# rechiever.net
KiCad netlist of a schematic drawn in EAGLE
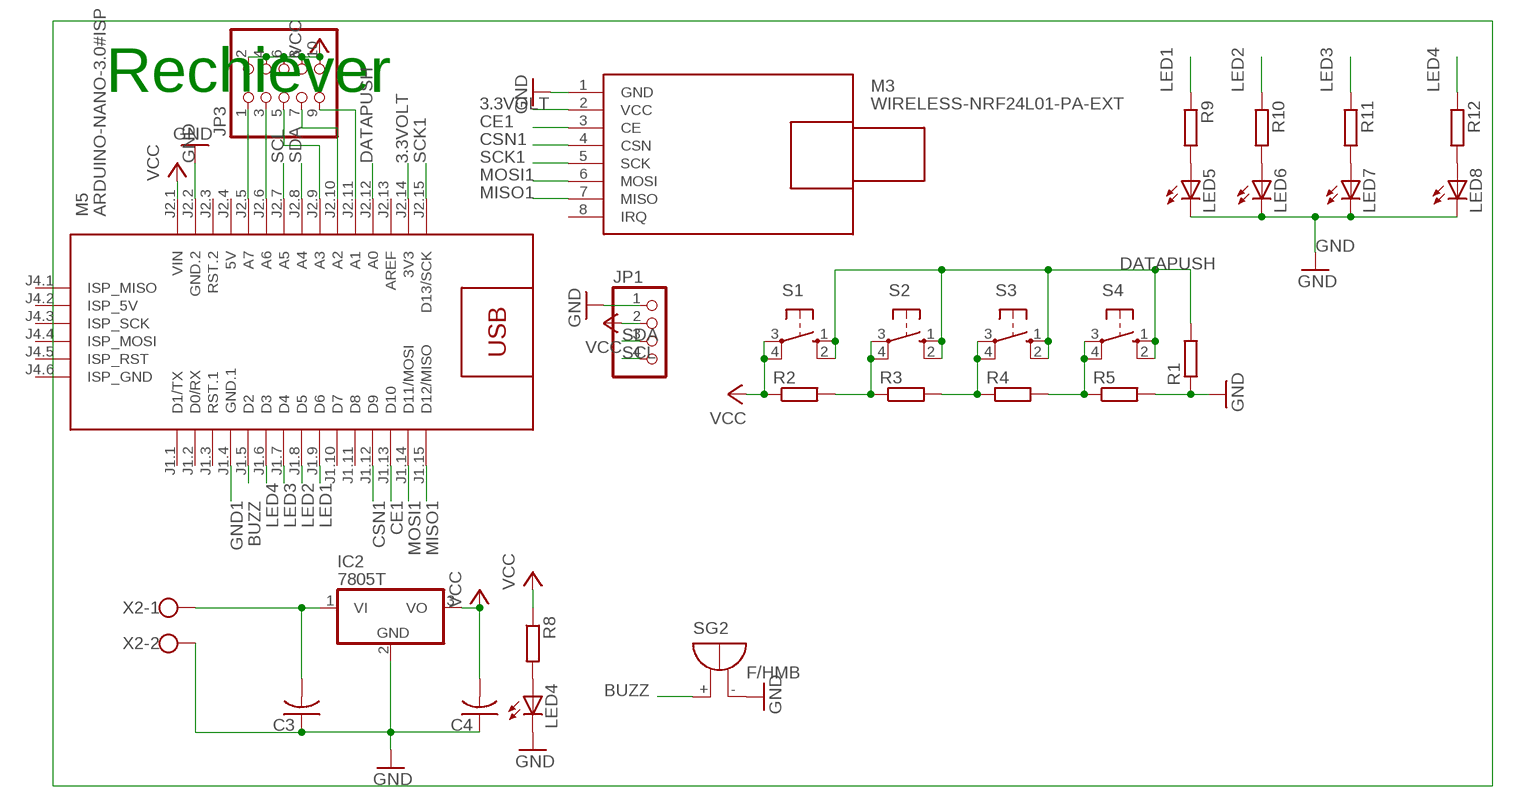
[diagram p0: schematic, sheet 1]

(export (version "E")
  (design (tool "Eeschema 10.0.6"))
  (components
    (comp (ref "C3")
      (value "C-US025-050X050")
      (footprint "eagle-import:C025-050X050")
      (libsource (lib "eagle-import") (part "C-US025-050X050"))
    )
    (comp (ref "C4")
      (value "C-US025-050X050")
      (footprint "eagle-import:C025-050X050")
      (libsource (lib "eagle-import") (part "C-US025-050X050"))
    )
    (comp (ref "IC2")
      (value "7805T")
      (footprint "eagle-import:TO220H")
      (libsource (lib "eagle-import") (part "78T05"))
    )
    (comp (ref "JP1")
      (value "PINHD-1X4")
      (footprint "eagle-import:1X04")
      (libsource (lib "eagle-import") (part "PINHD-1X4"))
    )
    (comp (ref "JP3")
      (value "PINHD-2X5")
      (footprint "eagle-import:2X05")
      (libsource (lib "eagle-import") (part "PINHD-2X5"))
    )
    (comp (ref "LED4")
      (value "LED3MM")
      (footprint "eagle-import:LED3MM")
      (libsource (lib "eagle-import") (part "LED3MM"))
    )
    (comp (ref "LED5")
      (value "LED5MM")
      (footprint "eagle-import:LED5MM")
      (libsource (lib "eagle-import") (part "LED5MM"))
    )
    (comp (ref "LED6")
      (value "LED5MM")
      (footprint "eagle-import:LED5MM")
      (libsource (lib "eagle-import") (part "LED5MM"))
    )
    (comp (ref "LED7")
      (value "LED5MM")
      (footprint "eagle-import:LED5MM")
      (libsource (lib "eagle-import") (part "LED5MM"))
    )
    (comp (ref "LED8")
      (value "LED5MM")
      (footprint "eagle-import:LED5MM")
      (libsource (lib "eagle-import") (part "LED5MM"))
    )
    (comp (ref "M3")
      (value "WIRELESS-NRF24L01-PA-EXT")
      (footprint "eagle-import:WIRELESS-NRF24L01-PA-EXT")
      (libsource (lib "eagle-import") (part "WIRELESS-NRF24L01-PA-EXT"))
    )
    (comp (ref "M5")
      (value "ARDUINO-NANO-3.0#ISP")
      (footprint "eagle-import:ARDUINO-NANO-3.0#ISP")
      (libsource (lib "eagle-import") (part "ARDUINO-NANO-3.0#ISP"))
    )
    (comp (ref "R1")
      (value "R-EU_0207/7")
      (footprint "eagle-import:0207_7")
      (libsource (lib "eagle-import") (part "R-EU_0207/7"))
    )
    (comp (ref "R2")
      (value "R-EU_0207/7")
      (footprint "eagle-import:0207_7")
      (libsource (lib "eagle-import") (part "R-EU_0207/7"))
    )
    (comp (ref "R3")
      (value "R-EU_0207/7")
      (footprint "eagle-import:0207_7")
      (libsource (lib "eagle-import") (part "R-EU_0207/7"))
    )
    (comp (ref "R4")
      (value "R-EU_0207/7")
      (footprint "eagle-import:0207_7")
      (libsource (lib "eagle-import") (part "R-EU_0207/7"))
    )
    (comp (ref "R5")
      (value "R-EU_0207/7")
      (footprint "eagle-import:0207_7")
      (libsource (lib "eagle-import") (part "R-EU_0207/7"))
    )
    (comp (ref "R8")
      (value "R-EU_0207/7")
      (footprint "eagle-import:0207_7")
      (libsource (lib "eagle-import") (part "R-EU_0207/7"))
    )
    (comp (ref "R9")
      (value "R-EU_0207/7")
      (footprint "eagle-import:0207_7")
      (libsource (lib "eagle-import") (part "R-EU_0207/7"))
    )
    (comp (ref "R10")
      (value "R-EU_0207/7")
      (footprint "eagle-import:0207_7")
      (libsource (lib "eagle-import") (part "R-EU_0207/7"))
    )
    (comp (ref "R11")
      (value "R-EU_0207/7")
      (footprint "eagle-import:0207_7")
      (libsource (lib "eagle-import") (part "R-EU_0207/7"))
    )
    (comp (ref "R12")
      (value "R-EU_0207/7")
      (footprint "eagle-import:0207_7")
      (libsource (lib "eagle-import") (part "R-EU_0207/7"))
    )
    (comp (ref "S1")
      (value "10-XX")
      (footprint "eagle-import:B3F-10XX")
      (fields (field (name "MPN") "B3F-1000"))
      (libsource (lib "eagle-import") (part "10-XX"))
    )
    (comp (ref "S2")
      (value "10-XX")
      (footprint "eagle-import:B3F-10XX")
      (fields (field (name "MPN") "B3F-1000"))
      (libsource (lib "eagle-import") (part "10-XX"))
    )
    (comp (ref "S3")
      (value "10-XX")
      (footprint "eagle-import:B3F-10XX")
      (fields (field (name "MPN") "B3F-1000"))
      (libsource (lib "eagle-import") (part "10-XX"))
    )
    (comp (ref "S4")
      (value "10-XX")
      (footprint "eagle-import:B3F-10XX")
      (fields (field (name "MPN") "B3F-1000"))
      (libsource (lib "eagle-import") (part "10-XX"))
    )
    (comp (ref "SG2")
      (value "F/HMB")
      (footprint "eagle-import:F_HMB")
      (libsource (lib "eagle-import") (part "F/HMB"))
    )
    (comp (ref "X2")
      (value "W237-102")
      (footprint "eagle-import:W237-102")
      (fields (field (name "MPN") "237-102"))
      (libsource (lib "eagle-import") (part "W237-102"))
    )
  )
  (nets
    (net (code "1") (name "/3.3VOLT") (class "Default")
      (node (ref "M3") (pin "2") (pinfunction "VCC_2") (pintype "power_in"))
      (node (ref "M5") (pin "J2.14") (pinfunction "3V3_J2.14") (pintype "power_in"))
    )
    (net (code "2") (name "/5V") (class "Default")
      (node (ref "M5") (pin "J2.4") (pinfunction "5V_J2.4") (pintype "power_in"))
    )
    (net (code "3") (name "/BUZZ") (class "Default")
      (node (ref "M5") (pin "J1.5") (pinfunction "D2_J1.5") (pintype "bidirectional"))
      (node (ref "SG2") (pin "+") (pinfunction "+_+") (pintype "passive"))
    )
    (net (code "4") (name "/CE1") (class "Default")
      (node (ref "M3") (pin "3") (pinfunction "CE_3") (pintype "bidirectional"))
      (node (ref "M5") (pin "J1.13") (pinfunction "D10_J1.13") (pintype "bidirectional"))
    )
    (net (code "5") (name "/CSN1") (class "Default")
      (node (ref "M3") (pin "4") (pinfunction "CSN_4") (pintype "bidirectional"))
      (node (ref "M5") (pin "J1.12") (pinfunction "D9_J1.12") (pintype "bidirectional"))
    )
    (net (code "6") (name "/DATAPUSH") (class "Default")
      (node (ref "M5") (pin "J2.12") (pinfunction "A0_J2.12") (pintype "bidirectional"))
      (node (ref "R1") (pin "2") (pinfunction "2_2") (pintype "passive"))
      (node (ref "S1") (pin "1") (pinfunction "S_1") (pintype "passive"))
      (node (ref "S1") (pin "2") (pinfunction "S1_2") (pintype "passive"))
      (node (ref "S2") (pin "1") (pinfunction "S_1") (pintype "passive"))
      (node (ref "S2") (pin "2") (pinfunction "S1_2") (pintype "passive"))
      (node (ref "S3") (pin "1") (pinfunction "S_1") (pintype "passive"))
      (node (ref "S3") (pin "2") (pinfunction "S1_2") (pintype "passive"))
      (node (ref "S4") (pin "1") (pinfunction "S_1") (pintype "passive"))
      (node (ref "S4") (pin "2") (pinfunction "S1_2") (pintype "passive"))
    )
    (net (code "7") (name "/GND1") (class "Default")
      (node (ref "M5") (pin "J1.4") (pinfunction "GND.1_J1.4") (pintype "power_in"))
    )
    (net (code "8") (name "/LED1") (class "Default")
      (node (ref "M5") (pin "J1.9") (pinfunction "D6_J1.9") (pintype "bidirectional"))
      (node (ref "R9") (pin "1") (pinfunction "1_1") (pintype "passive"))
    )
    (net (code "9") (name "/LED2") (class "Default")
      (node (ref "M5") (pin "J1.8") (pinfunction "D5_J1.8") (pintype "bidirectional"))
      (node (ref "R10") (pin "1") (pinfunction "1_1") (pintype "passive"))
    )
    (net (code "10") (name "/LED3") (class "Default")
      (node (ref "M5") (pin "J1.7") (pinfunction "D4_J1.7") (pintype "bidirectional"))
      (node (ref "R11") (pin "1") (pinfunction "1_1") (pintype "passive"))
    )
    (net (code "11") (name "/LED4") (class "Default")
      (node (ref "M5") (pin "J1.6") (pinfunction "D3_J1.6") (pintype "bidirectional"))
      (node (ref "R12") (pin "1") (pinfunction "1_1") (pintype "passive"))
    )
    (net (code "12") (name "/MISO1") (class "Default")
      (node (ref "M3") (pin "7") (pinfunction "MISO_7") (pintype "bidirectional"))
      (node (ref "M5") (pin "J1.15") (pinfunction "D12/MISO_J1.15") (pintype "bidirectional"))
    )
    (net (code "13") (name "/MOSI1") (class "Default")
      (node (ref "M3") (pin "6") (pinfunction "MOSI_6") (pintype "bidirectional"))
      (node (ref "M5") (pin "J1.14") (pinfunction "D11/MOSI_J1.14") (pintype "bidirectional"))
    )
    (net (code "15") (name "/SCK1") (class "Default")
      (node (ref "M3") (pin "5") (pinfunction "SCK_5") (pintype "bidirectional"))
      (node (ref "M5") (pin "J2.15") (pinfunction "D13/SCK_J2.15") (pintype "bidirectional"))
    )
    (net (code "16") (name "/SCL") (class "Default")
      (node (ref "JP1") (pin "4") (pinfunction "4_4") (pintype "passive"))
      (node (ref "M5") (pin "J2.7") (pinfunction "A5_J2.7") (pintype "bidirectional"))
    )
    (net (code "17") (name "/SDA") (class "Default")
      (node (ref "JP1") (pin "3") (pinfunction "3_3") (pintype "passive"))
      (node (ref "M5") (pin "J2.8") (pinfunction "A4_J2.8") (pintype "bidirectional"))
    )
    (net (code "18") (name "GND") (class "Default")
      (node (ref "C3") (pin "1") (pinfunction "1_1") (pintype "passive"))
      (node (ref "C4") (pin "1") (pinfunction "1_1") (pintype "passive"))
      (node (ref "IC2") (pin "2") (pinfunction "GND_2") (pintype "passive"))
      (node (ref "JP1") (pin "1") (pinfunction "1_1") (pintype "passive"))
      (node (ref "LED4") (pin "K") (pinfunction "C_K") (pintype "passive"))
      (node (ref "LED5") (pin "K") (pinfunction "C_K") (pintype "passive"))
      (node (ref "LED6") (pin "K") (pinfunction "C_K") (pintype "passive"))
      (node (ref "LED7") (pin "K") (pinfunction "C_K") (pintype "passive"))
      (node (ref "LED8") (pin "K") (pinfunction "C_K") (pintype "passive"))
      (node (ref "M3") (pin "1") (pinfunction "GND_1") (pintype "power_in"))
      (node (ref "M5") (pin "J2.2") (pinfunction "GND.2_J2.2") (pintype "power_in"))
      (node (ref "R1") (pin "1") (pinfunction "1_1") (pintype "passive"))
      (node (ref "R5") (pin "2") (pinfunction "2_2") (pintype "passive"))
      (node (ref "SG2") (pin "-") (pinfunction "-_-") (pintype "passive"))
      (node (ref "X2") (pin "2") (pinfunction "KL_2") (pintype "passive"))
    )
    (net (code "19") (name "Net-(IC2-VI)") (class "Default")
      (node (ref "C3") (pin "2") (pinfunction "2_2") (pintype "passive"))
      (node (ref "IC2") (pin "1") (pinfunction "VI_1") (pintype "input"))
      (node (ref "X2") (pin "1") (pinfunction "KL_1") (pintype "passive"))
    )
    (net (code "20") (name "Net-(LED4-PadA)") (class "Default")
      (node (ref "LED4") (pin "A") (pinfunction "A_A") (pintype "passive"))
      (node (ref "R8") (pin "2") (pinfunction "2_2") (pintype "passive"))
    )
    (net (code "21") (name "Net-(LED5-PadA)") (class "Default")
      (node (ref "LED5") (pin "A") (pinfunction "A_A") (pintype "passive"))
      (node (ref "R9") (pin "2") (pinfunction "2_2") (pintype "passive"))
    )
    (net (code "22") (name "Net-(LED6-PadA)") (class "Default")
      (node (ref "LED6") (pin "A") (pinfunction "A_A") (pintype "passive"))
      (node (ref "R10") (pin "2") (pinfunction "2_2") (pintype "passive"))
    )
    (net (code "23") (name "Net-(LED7-PadA)") (class "Default")
      (node (ref "LED7") (pin "A") (pinfunction "A_A") (pintype "passive"))
      (node (ref "R11") (pin "2") (pinfunction "2_2") (pintype "passive"))
    )
    (net (code "24") (name "Net-(LED8-PadA)") (class "Default")
      (node (ref "LED8") (pin "A") (pinfunction "A_A") (pintype "passive"))
      (node (ref "R12") (pin "2") (pinfunction "2_2") (pintype "passive"))
    )
    (net (code "25") (name "Net-(M5-A1)") (class "Default")
      (node (ref "JP3") (pin "9") (pinfunction "9_9") (pintype "passive"))
      (node (ref "M5") (pin "J2.11") (pinfunction "A1_J2.11") (pintype "bidirectional"))
    )
    (net (code "26") (name "Net-(M5-A2)") (class "Default")
      (node (ref "JP3") (pin "7") (pinfunction "7_7") (pintype "passive"))
      (node (ref "M5") (pin "J2.10") (pinfunction "A2_J2.10") (pintype "bidirectional"))
    )
    (net (code "27") (name "Net-(M5-A3)") (class "Default")
      (node (ref "JP3") (pin "5") (pinfunction "5_5") (pintype "passive"))
      (node (ref "M5") (pin "J2.9") (pinfunction "A3_J2.9") (pintype "bidirectional"))
    )
    (net (code "28") (name "Net-(M5-A6)") (class "Default")
      (node (ref "JP3") (pin "3") (pinfunction "3_3") (pintype "passive"))
      (node (ref "M5") (pin "J2.6") (pinfunction "A6_J2.6") (pintype "bidirectional"))
    )
    (net (code "29") (name "Net-(M5-A7)") (class "Default")
      (node (ref "JP3") (pin "1") (pinfunction "1_1") (pintype "passive"))
      (node (ref "M5") (pin "J2.5") (pinfunction "A7_J2.5") (pintype "bidirectional"))
    )
    (net (code "30") (name "Net-(S2-P)") (class "Default")
      (node (ref "R2") (pin "2") (pinfunction "2_2") (pintype "passive"))
      (node (ref "R3") (pin "1") (pinfunction "1_1") (pintype "passive"))
      (node (ref "S2") (pin "3") (pinfunction "P_3") (pintype "passive"))
      (node (ref "S2") (pin "4") (pinfunction "P1_4") (pintype "passive"))
    )
    (net (code "31") (name "Net-(S3-P)") (class "Default")
      (node (ref "R3") (pin "2") (pinfunction "2_2") (pintype "passive"))
      (node (ref "R4") (pin "1") (pinfunction "1_1") (pintype "passive"))
      (node (ref "S3") (pin "3") (pinfunction "P_3") (pintype "passive"))
      (node (ref "S3") (pin "4") (pinfunction "P1_4") (pintype "passive"))
    )
    (net (code "32") (name "Net-(S4-P)") (class "Default")
      (node (ref "R4") (pin "2") (pinfunction "2_2") (pintype "passive"))
      (node (ref "R5") (pin "1") (pinfunction "1_1") (pintype "passive"))
      (node (ref "S4") (pin "3") (pinfunction "P_3") (pintype "passive"))
      (node (ref "S4") (pin "4") (pinfunction "P1_4") (pintype "passive"))
    )
    (net (code "33") (name "VCC") (class "Default")
      (node (ref "C4") (pin "2") (pinfunction "2_2") (pintype "passive"))
      (node (ref "IC2") (pin "3") (pinfunction "VO_3") (pintype "passive"))
      (node (ref "JP1") (pin "2") (pinfunction "2_2") (pintype "passive"))
      (node (ref "JP3") (pin "10") (pinfunction "10_10") (pintype "passive"))
      (node (ref "JP3") (pin "2") (pinfunction "2_2") (pintype "passive"))
      (node (ref "JP3") (pin "4") (pinfunction "4_4") (pintype "passive"))
      (node (ref "JP3") (pin "6") (pinfunction "6_6") (pintype "passive"))
      (node (ref "JP3") (pin "8") (pinfunction "8_8") (pintype "passive"))
      (node (ref "M5") (pin "J2.1") (pinfunction "VIN_J2.1") (pintype "power_in"))
      (node (ref "R2") (pin "1") (pinfunction "1_1") (pintype "passive"))
      (node (ref "R8") (pin "1") (pinfunction "1_1") (pintype "passive"))
      (node (ref "S1") (pin "3") (pinfunction "P_3") (pintype "passive"))
      (node (ref "S1") (pin "4") (pinfunction "P1_4") (pintype "passive"))
    )
    (net (code "34") (name "unconnected-(M3-IRQ-Pad8)") (class "Default")
      (node (ref "M3") (pin "8") (pinfunction "IRQ_8") (pintype "bidirectional"))
    )
    (net (code "35") (name "unconnected-(M5-AREF-PadJ2.13)") (class "Default")
      (node (ref "M5") (pin "J2.13") (pinfunction "AREF_J2.13") (pintype "bidirectional"))
    )
    (net (code "36") (name "unconnected-(M5-D0{slash}RX-PadJ1.2)") (class "Default")
      (node (ref "M5") (pin "J1.2") (pinfunction "D0/RX_J1.2") (pintype "bidirectional"))
    )
    (net (code "37") (name "unconnected-(M5-D1{slash}TX-PadJ1.1)") (class "Default")
      (node (ref "M5") (pin "J1.1") (pinfunction "D1/TX_J1.1") (pintype "bidirectional"))
    )
    (net (code "38") (name "unconnected-(M5-D7-PadJ1.10)") (class "Default")
      (node (ref "M5") (pin "J1.10") (pinfunction "D7_J1.10") (pintype "bidirectional"))
    )
    (net (code "39") (name "unconnected-(M5-D8-PadJ1.11)") (class "Default")
      (node (ref "M5") (pin "J1.11") (pinfunction "D8_J1.11") (pintype "bidirectional"))
    )
    (net (code "40") (name "unconnected-(M5-ISP_5V-PadJ4.2)") (class "Default")
      (node (ref "M5") (pin "J4.2") (pinfunction "ISP_5V_J4.2") (pintype "bidirectional"))
    )
    (net (code "41") (name "unconnected-(M5-ISP_GND-PadJ4.6)") (class "Default")
      (node (ref "M5") (pin "J4.6") (pinfunction "ISP_GND_J4.6") (pintype "bidirectional"))
    )
    (net (code "42") (name "unconnected-(M5-ISP_MISO-PadJ4.1)") (class "Default")
      (node (ref "M5") (pin "J4.1") (pinfunction "ISP_MISO_J4.1") (pintype "bidirectional"))
    )
    (net (code "43") (name "unconnected-(M5-ISP_MOSI-PadJ4.4)") (class "Default")
      (node (ref "M5") (pin "J4.4") (pinfunction "ISP_MOSI_J4.4") (pintype "bidirectional"))
    )
    (net (code "44") (name "unconnected-(M5-ISP_RST-PadJ4.5)") (class "Default")
      (node (ref "M5") (pin "J4.5") (pinfunction "ISP_RST_J4.5") (pintype "bidirectional"))
    )
    (net (code "45") (name "unconnected-(M5-ISP_SCK-PadJ4.3)") (class "Default")
      (node (ref "M5") (pin "J4.3") (pinfunction "ISP_SCK_J4.3") (pintype "bidirectional"))
    )
    (net (code "46") (name "unconnected-(M5-RST.1-PadJ1.3)") (class "Default")
      (node (ref "M5") (pin "J1.3") (pinfunction "RST.1_J1.3") (pintype "bidirectional"))
    )
    (net (code "47") (name "unconnected-(M5-RST.2-PadJ2.3)") (class "Default")
      (node (ref "M5") (pin "J2.3") (pinfunction "RST.2_J2.3") (pintype "bidirectional"))
    )
  )
)
